# HeatElement.net
KiCad netlist of a schematic drawn in Altium Designer
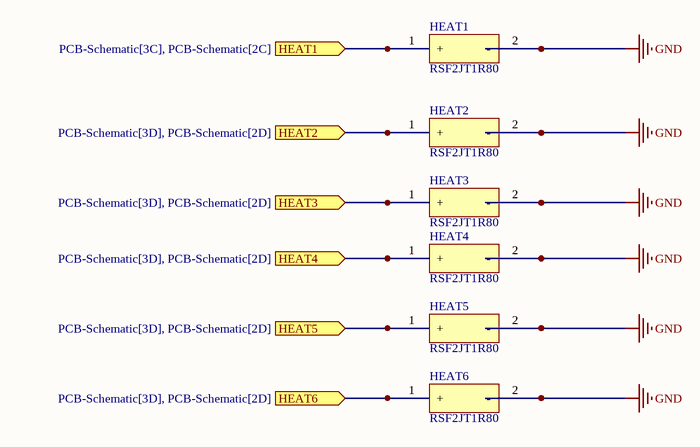
[diagram p0: HeatElement.SchDoc]

(export (version "E")
  (design (tool "Eeschema 10.0.6"))
  (components
    (comp (ref "HEAT1")
      (value "RSF2JT1R80")
      (footprint "PCBComponent_1")
      (libsource (lib "TMP6331DYAR") (part "Component_1"))
    )
    (comp (ref "HEAT2")
      (value "RSF2JT1R80")
      (footprint "PCBComponent_1")
      (libsource (lib "TMP6331DYAR") (part "Component_1"))
    )
    (comp (ref "HEAT3")
      (value "RSF2JT1R80")
      (footprint "PCBComponent_1")
      (libsource (lib "TMP6331DYAR") (part "Component_1"))
    )
    (comp (ref "HEAT4")
      (value "RSF2JT1R80")
      (footprint "PCBComponent_1")
      (libsource (lib "TMP6331DYAR") (part "Component_1"))
    )
    (comp (ref "HEAT5")
      (value "RSF2JT1R80")
      (footprint "PCBComponent_1")
      (libsource (lib "TMP6331DYAR") (part "Component_1"))
    )
    (comp (ref "HEAT6")
      (value "RSF2JT1R80")
      (footprint "PCBComponent_1")
      (libsource (lib "TMP6331DYAR") (part "Component_1"))
    )
  )
  (nets
    (net (code "1") (name "/HEAT1") (class "Default")
      (node (ref "HEAT1") (pin "1") (pinfunction "+_1") (pintype "passive"))
    )
    (net (code "2") (name "/HEAT2") (class "Default")
      (node (ref "HEAT2") (pin "1") (pinfunction "+_1") (pintype "passive"))
    )
    (net (code "3") (name "/HEAT3") (class "Default")
      (node (ref "HEAT3") (pin "1") (pinfunction "+_1") (pintype "passive"))
    )
    (net (code "4") (name "/HEAT4") (class "Default")
      (node (ref "HEAT4") (pin "1") (pinfunction "+_1") (pintype "passive"))
    )
    (net (code "5") (name "/HEAT5") (class "Default")
      (node (ref "HEAT5") (pin "1") (pinfunction "+_1") (pintype "passive"))
    )
    (net (code "6") (name "/HEAT6") (class "Default")
      (node (ref "HEAT6") (pin "1") (pinfunction "+_1") (pintype "passive"))
    )
    (net (code "7") (name "GND") (class "Default")
      (node (ref "HEAT1") (pin "2") (pinfunction "-_2") (pintype "passive"))
      (node (ref "HEAT2") (pin "2") (pinfunction "-_2") (pintype "passive"))
      (node (ref "HEAT3") (pin "2") (pinfunction "-_2") (pintype "passive"))
      (node (ref "HEAT4") (pin "2") (pinfunction "-_2") (pintype "passive"))
      (node (ref "HEAT5") (pin "2") (pinfunction "-_2") (pintype "passive"))
      (node (ref "HEAT6") (pin "2") (pinfunction "-_2") (pintype "passive"))
    )
  )
)
